# Motor_Driver_HIP4082_TPH1R403_Board_V2_0.net
KiCad netlist of a schematic drawn in Altium Designer
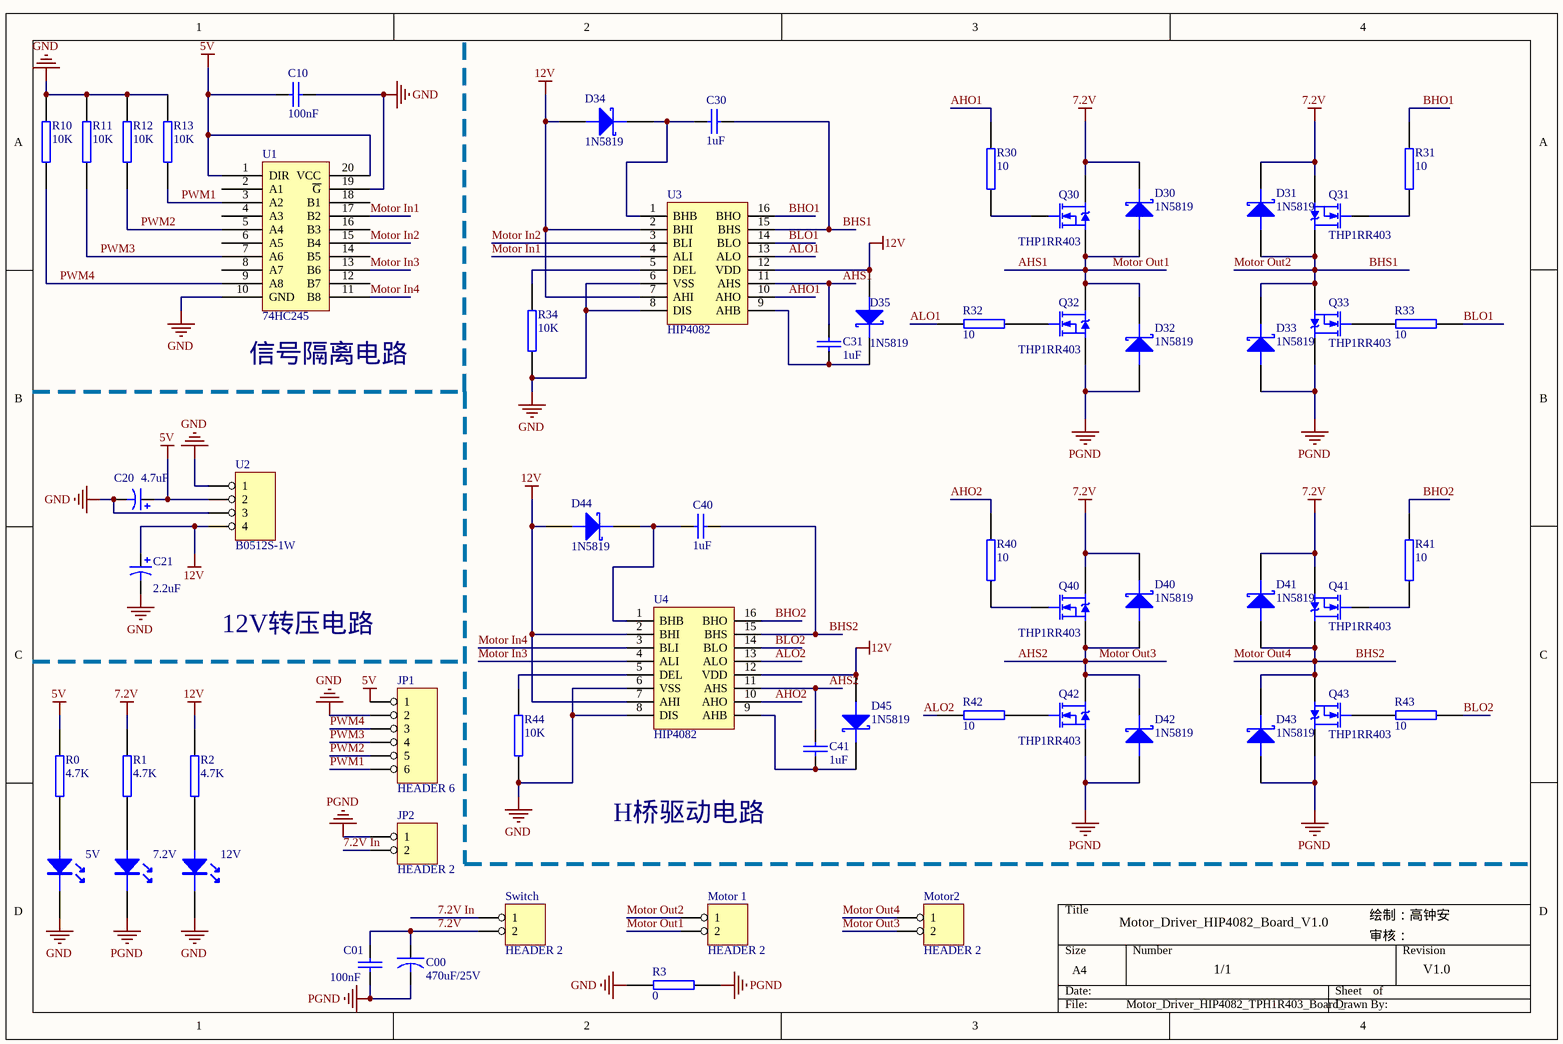
[diagram p0: Motor_Driver_HIP4082_TPH1R403_Board_V2.0.SchDoc]

(export (version "E")
  (design (tool "Eeschema 10.0.6"))
  (components
    (comp (ref "5V") (value "~") (footprint "0805_LED_S1") (libsource (lib "Protel99Lib_SCH") (part "LED")))
    (comp (ref "7.2V") (value "~") (footprint "0805_LED_S1") (libsource (lib "Protel99Lib_SCH") (part "LED")))
    (comp (ref "12V") (value "~") (footprint "0805_LED_S1") (libsource (lib "Protel99Lib_SCH") (part "LED")))
    (comp (ref "C00")
      (value "470uF/25V")
      (footprint "RB.2/.4")
      (description "Capacitor")
      (libsource (lib "Protel99Lib_SCH") (part "CAPACITOR"))
    )
    (comp (ref "C01")
      (value "100nF")
      (footprint "0805C")
      (description "Capacitor")
      (libsource (lib "Protel99Lib_SCH") (part "CAP"))
    )
    (comp (ref "C10")
      (value "100nF")
      (footprint "0603_C")
      (description "Capacitor")
      (libsource (lib "Protel99Lib_SCH") (part "CAP"))
    )
    (comp (ref "C20")
      (value "4.7uF")
      (footprint "3528")
      (description "Polarized Capacitor (Surface Mount)")
      (fields (field (name "PUBLISHER") "Altium Limited"))
      (libsource (lib "Miscellaneous Devices") (part "Cap Pol3"))
    )
    (comp (ref "C21")
      (value "2.2uF")
      (footprint "3528")
      (description "Polarized Capacitor (Surface Mount)")
      (fields (field (name "PUBLISHER") "Altium Limited"))
      (libsource (lib "Miscellaneous Devices") (part "Cap Pol3"))
    )
    (comp (ref "C30")
      (value "1uF")
      (footprint "0603C")
      (description "Capacitor")
      (libsource (lib "Protel99Lib_SCH") (part "CAP"))
    )
    (comp (ref "C31")
      (value "1uF")
      (footprint "0603C")
      (description "Capacitor")
      (libsource (lib "Protel99Lib_SCH") (part "CAP"))
    )
    (comp (ref "C40")
      (value "1uF")
      (footprint "0603_C")
      (description "Capacitor")
      (libsource (lib "Protel99Lib_SCH") (part "CAP"))
    )
    (comp (ref "C41")
      (value "1uF")
      (footprint "0603_C")
      (description "Capacitor")
      (libsource (lib "Protel99Lib_SCH") (part "CAP"))
    )
    (comp (ref "D30")
      (value "1N5819")
      (footprint "SOD-323")
      (description "Schottky Diode")
      (libsource (lib "Protel99Lib_SCH") (part "DIODE SCHOTTKY"))
    )
    (comp (ref "D31")
      (value "1N5819")
      (footprint "SOD-323")
      (description "Schottky Diode")
      (libsource (lib "Protel99Lib_SCH") (part "DIODE SCHOTTKY"))
    )
    (comp (ref "D32")
      (value "1N5819")
      (footprint "SOD-323")
      (description "Schottky Diode")
      (libsource (lib "Protel99Lib_SCH") (part "DIODE SCHOTTKY"))
    )
    (comp (ref "D33")
      (value "1N5819")
      (footprint "SOD-323")
      (description "Schottky Diode")
      (libsource (lib "Protel99Lib_SCH") (part "DIODE SCHOTTKY"))
    )
    (comp (ref "D34")
      (value "1N5819")
      (footprint "SOD-323")
      (description "Schottky Diode")
      (libsource (lib "Protel99Lib_SCH") (part "DIODE SCHOTTKY"))
    )
    (comp (ref "D35")
      (value "1N5819")
      (footprint "SOD-323")
      (description "Schottky Diode")
      (libsource (lib "Protel99Lib_SCH") (part "DIODE SCHOTTKY"))
    )
    (comp (ref "D40")
      (value "1N5819")
      (footprint "SOD-323")
      (description "Schottky Diode")
      (libsource (lib "Protel99Lib_SCH") (part "DIODE SCHOTTKY"))
    )
    (comp (ref "D41")
      (value "1N5819")
      (footprint "SOD-323")
      (description "Schottky Diode")
      (libsource (lib "Protel99Lib_SCH") (part "DIODE SCHOTTKY"))
    )
    (comp (ref "D42")
      (value "1N5819")
      (footprint "SOD-323")
      (description "Schottky Diode")
      (libsource (lib "Protel99Lib_SCH") (part "DIODE SCHOTTKY"))
    )
    (comp (ref "D43")
      (value "1N5819")
      (footprint "SOD-323")
      (description "Schottky Diode")
      (libsource (lib "Protel99Lib_SCH") (part "DIODE SCHOTTKY"))
    )
    (comp (ref "D44")
      (value "1N5819")
      (footprint "SOD-323")
      (description "Schottky Diode")
      (libsource (lib "Protel99Lib_SCH") (part "DIODE SCHOTTKY"))
    )
    (comp (ref "D45")
      (value "1N5819")
      (footprint "SOD-323")
      (description "Schottky Diode")
      (libsource (lib "Protel99Lib_SCH") (part "DIODE SCHOTTKY"))
    )
    (comp (ref "JP1")
      (value "HEADER 6")
      (footprint "SIP6N")
      (libsource (lib "Protel99Lib_SCH") (part "HEADER 6"))
    )
    (comp (ref "JP2")
      (value "HEADER 2")
      (footprint "T_Type_Adapter")
      (libsource (lib "Protel99Lib_SCH") (part "HEADER 2"))
    )
    (comp (ref "Motor 1")
      (value "HEADER 2")
      (footprint "KF301-2P")
      (libsource (lib "Protel99Lib_SCH") (part "HEADER 2"))
    )
    (comp (ref "Motor2")
      (value "HEADER 2")
      (footprint "KF301-2P")
      (libsource (lib "Protel99Lib_SCH") (part "HEADER 2"))
    )
    (comp (ref "Q30")
      (value "THP1RR403")
      (footprint "SOP_Advanced")
      (description "N-Channel MOSFET")
      (fields (field (name "PUBLISHER") "Altium Limited"))
      (libsource (lib "0.5 - 场效应管-可控硅") (part "MOSFET-N"))
    )
    (comp (ref "Q31")
      (value "THP1RR403")
      (footprint "SOP_Advanced")
      (description "N-Channel MOSFET")
      (fields (field (name "PUBLISHER") "Altium Limited"))
      (libsource (lib "0.5 - 场效应管-可控硅") (part "MOSFET-N"))
    )
    (comp (ref "Q32")
      (value "THP1RR403")
      (footprint "SOP_Advanced")
      (description "N-Channel MOSFET")
      (fields (field (name "PUBLISHER") "Altium Limited"))
      (libsource (lib "0.5 - 场效应管-可控硅") (part "MOSFET-N"))
    )
    (comp (ref "Q33")
      (value "THP1RR403")
      (footprint "SOP_Advanced")
      (description "N-Channel MOSFET")
      (fields (field (name "PUBLISHER") "Altium Limited"))
      (libsource (lib "0.5 - 场效应管-可控硅") (part "MOSFET-N"))
    )
    (comp (ref "Q40")
      (value "THP1RR403")
      (footprint "SOP_Advanced")
      (description "N-Channel MOSFET")
      (fields (field (name "PUBLISHER") "Altium Limited"))
      (libsource (lib "0.5 - 场效应管-可控硅") (part "MOSFET-N"))
    )
    (comp (ref "Q41")
      (value "THP1RR403")
      (footprint "SOP_Advanced")
      (description "N-Channel MOSFET")
      (fields (field (name "PUBLISHER") "Altium Limited"))
      (libsource (lib "0.5 - 场效应管-可控硅") (part "MOSFET-N"))
    )
    (comp (ref "Q42")
      (value "THP1RR403")
      (footprint "SOP_Advanced")
      (description "N-Channel MOSFET")
      (fields (field (name "PUBLISHER") "Altium Limited"))
      (libsource (lib "0.5 - 场效应管-可控硅") (part "MOSFET-N"))
    )
    (comp (ref "Q43")
      (value "THP1RR403")
      (footprint "SOP_Advanced")
      (description "N-Channel MOSFET")
      (fields (field (name "PUBLISHER") "Altium Limited"))
      (libsource (lib "0.5 - 场效应管-可控硅") (part "MOSFET-N"))
    )
    (comp (ref "R0") (value "4.7K") (footprint "0603_R") (libsource (lib "Protel99Lib_SCH") (part "RES2")))
    (comp (ref "R1") (value "4.7K") (footprint "0603_R") (libsource (lib "Protel99Lib_SCH") (part "RES2")))
    (comp (ref "R2") (value "4.7K") (footprint "0603_R") (libsource (lib "Protel99Lib_SCH") (part "RES2")))
    (comp (ref "R3") (value "0") (footprint "0805") (libsource (lib "Protel99Lib_SCH") (part "RES2")))
    (comp (ref "R10") (value "10K") (footprint "0603_R") (libsource (lib "") (part "RES2_1")))
    (comp (ref "R11") (value "10K") (footprint "0603_R") (libsource (lib "") (part "RES2_1")))
    (comp (ref "R12") (value "10K") (footprint "0603_R") (libsource (lib "") (part "RES2_1")))
    (comp (ref "R13") (value "10K") (footprint "0603_R") (libsource (lib "") (part "RES2_1")))
    (comp (ref "R30") (value "10") (footprint "0805") (libsource (lib "Protel99Lib_SCH") (part "RES2")))
    (comp (ref "R31") (value "10") (footprint "0805") (libsource (lib "Protel99Lib_SCH") (part "RES2")))
    (comp (ref "R32") (value "10") (footprint "0805") (libsource (lib "Protel99Lib_SCH") (part "RES2")))
    (comp (ref "R33") (value "10") (footprint "0805") (libsource (lib "Protel99Lib_SCH") (part "RES2")))
    (comp (ref "R34") (value "10K") (footprint "0603_R") (libsource (lib "Protel99Lib_SCH") (part "RES2")))
    (comp (ref "R40") (value "10") (footprint "0805") (libsource (lib "Protel99Lib_SCH") (part "RES2")))
    (comp (ref "R41") (value "10") (footprint "0805") (libsource (lib "Protel99Lib_SCH") (part "RES2")))
    (comp (ref "R42") (value "10") (footprint "0805") (libsource (lib "Protel99Lib_SCH") (part "RES2")))
    (comp (ref "R43") (value "10") (footprint "0805") (libsource (lib "Protel99Lib_SCH") (part "RES2")))
    (comp (ref "R44") (value "10K") (footprint "0603_R") (libsource (lib "Protel99Lib_SCH") (part "RES2")))
    (comp (ref "Switch")
      (value "HEADER 2")
      (footprint "SWITCH-MINI")
      (libsource (lib "Protel99Lib_SCH") (part "HEADER 2"))
    )
    (comp (ref "U1") (value "74HC245") (footprint "SOP20") (libsource (lib "BaseLib_SCH") (part "74HC245")))
    (comp (ref "U2")
      (value "B0512S-1W")
      (footprint "SIP4_B_S-1W")
      (description "4 Pin Header")
      (libsource (lib "Protel99Lib_SCH") (part "4 HEADER"))
    )
    (comp (ref "U3")
      (value "HIP4082")
      (footprint "SOP-16_208mil")
      (libsource (lib "Motor_Driver_HIP4082_Board_V1.0") (part "HIP4082"))
    )
    (comp (ref "U4")
      (value "HIP4082")
      (footprint "SOP-16_208mil")
      (libsource (lib "Motor_Driver_HIP4082_Board_V1.0") (part "HIP4082"))
    )
  )
  (nets
    (net (code "1") (name "/7.2V In") (class "Default")
      (node (ref "JP2") (pin "2") (pinfunction "2_2") (pintype "passive"))
      (node (ref "Switch") (pin "1") (pinfunction "1_1") (pintype "passive"))
    )
    (net (code "2") (name "/AHO1") (class "Default")
      (node (ref "R30") (pin "2") (pinfunction "2_2") (pintype "passive"))
      (node (ref "U3") (pin "10") (pinfunction "AHO_10") (pintype "passive"))
    )
    (net (code "3") (name "/AHO2") (class "Default")
      (node (ref "R40") (pin "2") (pinfunction "2_2") (pintype "passive"))
      (node (ref "U4") (pin "10") (pinfunction "AHO_10") (pintype "passive"))
    )
    (net (code "4") (name "/AHS1") (class "Default")
      (node (ref "C31") (pin "2") (pinfunction "2_2") (pintype "passive"))
      (node (ref "D30") (pin "1") (pinfunction "A_1") (pintype "passive"))
      (node (ref "D32") (pin "2") (pinfunction "K_2") (pintype "passive"))
      (node (ref "Motor 1") (pin "2") (pinfunction "2_2") (pintype "passive"))
      (node (ref "Q30") (pin "3") (pinfunction "S_3") (pintype "passive"))
      (node (ref "Q32") (pin "1") (pinfunction "D_1") (pintype "passive"))
      (node (ref "U3") (pin "11") (pinfunction "AHS_11") (pintype "passive"))
    )
    (net (code "5") (name "/AHS2") (class "Default")
      (node (ref "C41") (pin "2") (pinfunction "2_2") (pintype "passive"))
      (node (ref "D40") (pin "1") (pinfunction "A_1") (pintype "passive"))
      (node (ref "D42") (pin "2") (pinfunction "K_2") (pintype "passive"))
      (node (ref "Motor2") (pin "2") (pinfunction "2_2") (pintype "passive"))
      (node (ref "Q40") (pin "3") (pinfunction "S_3") (pintype "passive"))
      (node (ref "Q42") (pin "1") (pinfunction "D_1") (pintype "passive"))
      (node (ref "U4") (pin "11") (pinfunction "AHS_11") (pintype "passive"))
    )
    (net (code "6") (name "/ALO1") (class "Default")
      (node (ref "R32") (pin "2") (pinfunction "2_2") (pintype "passive"))
      (node (ref "U3") (pin "13") (pinfunction "ALO_13") (pintype "passive"))
    )
    (net (code "7") (name "/ALO2") (class "Default")
      (node (ref "R42") (pin "2") (pinfunction "2_2") (pintype "passive"))
      (node (ref "U4") (pin "13") (pinfunction "ALO_13") (pintype "passive"))
    )
    (net (code "8") (name "/BHO1") (class "Default")
      (node (ref "R31") (pin "2") (pinfunction "2_2") (pintype "passive"))
      (node (ref "U3") (pin "16") (pinfunction "BHO_16") (pintype "passive"))
    )
    (net (code "9") (name "/BHO2") (class "Default")
      (node (ref "R41") (pin "2") (pinfunction "2_2") (pintype "passive"))
      (node (ref "U4") (pin "16") (pinfunction "BHO_16") (pintype "passive"))
    )
    (net (code "10") (name "/BHS1") (class "Default")
      (node (ref "C30") (pin "2") (pinfunction "2_2") (pintype "passive"))
      (node (ref "D31") (pin "1") (pinfunction "A_1") (pintype "passive"))
      (node (ref "D33") (pin "2") (pinfunction "K_2") (pintype "passive"))
      (node (ref "Motor 1") (pin "1") (pinfunction "1_1") (pintype "passive"))
      (node (ref "Q31") (pin "1") (pinfunction "D_1") (pintype "passive"))
      (node (ref "Q33") (pin "3") (pinfunction "S_3") (pintype "passive"))
      (node (ref "U3") (pin "15") (pinfunction "BHS_15") (pintype "passive"))
    )
    (net (code "11") (name "/BHS2") (class "Default")
      (node (ref "C40") (pin "2") (pinfunction "2_2") (pintype "passive"))
      (node (ref "D41") (pin "1") (pinfunction "A_1") (pintype "passive"))
      (node (ref "D43") (pin "2") (pinfunction "K_2") (pintype "passive"))
      (node (ref "Motor2") (pin "1") (pinfunction "1_1") (pintype "passive"))
      (node (ref "Q41") (pin "1") (pinfunction "D_1") (pintype "passive"))
      (node (ref "Q43") (pin "3") (pinfunction "S_3") (pintype "passive"))
      (node (ref "U4") (pin "15") (pinfunction "BHS_15") (pintype "passive"))
    )
    (net (code "12") (name "/BLO1") (class "Default")
      (node (ref "R33") (pin "1") (pinfunction "1_1") (pintype "passive"))
      (node (ref "U3") (pin "14") (pinfunction "BLO_14") (pintype "passive"))
    )
    (net (code "13") (name "/BLO2") (class "Default")
      (node (ref "R43") (pin "1") (pinfunction "1_1") (pintype "passive"))
      (node (ref "U4") (pin "14") (pinfunction "BLO_14") (pintype "passive"))
    )
    (net (code "14") (name "/Motor In1") (class "Default")
      (node (ref "U1") (pin "17") (pinfunction "B2_17") (pintype "passive"))
      (node (ref "U3") (pin "4") (pinfunction "ALI_4") (pintype "passive"))
    )
    (net (code "15") (name "/Motor In2") (class "Default")
      (node (ref "U1") (pin "15") (pinfunction "B4_15") (pintype "passive"))
      (node (ref "U3") (pin "3") (pinfunction "BLI_3") (pintype "passive"))
    )
    (net (code "16") (name "/Motor In3") (class "Default")
      (node (ref "U1") (pin "13") (pinfunction "B6_13") (pintype "passive"))
      (node (ref "U4") (pin "4") (pinfunction "ALI_4") (pintype "passive"))
    )
    (net (code "17") (name "/Motor In4") (class "Default")
      (node (ref "U1") (pin "11") (pinfunction "B8_11") (pintype "passive"))
      (node (ref "U4") (pin "3") (pinfunction "BLI_3") (pintype "passive"))
    )
    (net (code "18") (name "/PWM1") (class "Default")
      (node (ref "JP1") (pin "6") (pinfunction "6_6") (pintype "passive"))
      (node (ref "R13") (pin "1") (pinfunction "1_1") (pintype "passive"))
      (node (ref "U1") (pin "3") (pinfunction "A2_3") (pintype "passive"))
    )
    (net (code "19") (name "/PWM2") (class "Default")
      (node (ref "JP1") (pin "5") (pinfunction "5_5") (pintype "passive"))
      (node (ref "R12") (pin "1") (pinfunction "1_1") (pintype "passive"))
      (node (ref "U1") (pin "5") (pinfunction "A4_5") (pintype "passive"))
    )
    (net (code "20") (name "/PWM3") (class "Default")
      (node (ref "JP1") (pin "4") (pinfunction "4_4") (pintype "passive"))
      (node (ref "R11") (pin "2") (pinfunction "2_2") (pintype "passive"))
      (node (ref "U1") (pin "7") (pinfunction "A6_7") (pintype "passive"))
    )
    (net (code "21") (name "/PWM4") (class "Default")
      (node (ref "JP1") (pin "3") (pinfunction "3_3") (pintype "passive"))
      (node (ref "R10") (pin "1") (pinfunction "1_1") (pintype "passive"))
      (node (ref "U1") (pin "9") (pinfunction "A8_9") (pintype "passive"))
    )
    (net (code "22") (name "5V") (class "Default")
      (node (ref "C10") (pin "1") (pinfunction "1_1") (pintype "passive"))
      (node (ref "C20") (pin "1") (pinfunction "1_1") (pintype "passive"))
      (node (ref "JP1") (pin "1") (pinfunction "1_1") (pintype "passive"))
      (node (ref "R0") (pin "2") (pinfunction "2_2") (pintype "passive"))
      (node (ref "U1") (pin "1") (pinfunction "DIR_1") (pintype "passive"))
      (node (ref "U1") (pin "20") (pinfunction "VCC_20") (pintype "passive"))
      (node (ref "U2") (pin "2") (pinfunction "2_2") (pintype "passive"))
    )
    (net (code "23") (name "7.2V") (class "Default")
      (node (ref "C00") (pin "1") (pinfunction "1_1") (pintype "passive"))
      (node (ref "C01") (pin "2") (pinfunction "2_2") (pintype "passive"))
      (node (ref "D30") (pin "2") (pinfunction "K_2") (pintype "passive"))
      (node (ref "D31") (pin "2") (pinfunction "K_2") (pintype "passive"))
      (node (ref "D40") (pin "2") (pinfunction "K_2") (pintype "passive"))
      (node (ref "D41") (pin "2") (pinfunction "K_2") (pintype "passive"))
      (node (ref "Q30") (pin "1") (pinfunction "D_1") (pintype "passive"))
      (node (ref "Q31") (pin "3") (pinfunction "S_3") (pintype "passive"))
      (node (ref "Q40") (pin "1") (pinfunction "D_1") (pintype "passive"))
      (node (ref "Q41") (pin "3") (pinfunction "S_3") (pintype "passive"))
      (node (ref "R1") (pin "2") (pinfunction "2_2") (pintype "passive"))
      (node (ref "Switch") (pin "2") (pinfunction "2_2") (pintype "passive"))
    )
    (net (code "24") (name "12V") (class "Default")
      (node (ref "C21") (pin "1") (pinfunction "1_1") (pintype "passive"))
      (node (ref "D34") (pin "1") (pinfunction "A_1") (pintype "passive"))
      (node (ref "D35") (pin "1") (pinfunction "A_1") (pintype "passive"))
      (node (ref "D44") (pin "1") (pinfunction "A_1") (pintype "passive"))
      (node (ref "D45") (pin "1") (pinfunction "A_1") (pintype "passive"))
      (node (ref "R2") (pin "2") (pinfunction "2_2") (pintype "passive"))
      (node (ref "U2") (pin "4") (pinfunction "4_4") (pintype "passive"))
      (node (ref "U3") (pin "12") (pinfunction "VDD_12") (pintype "passive"))
      (node (ref "U3") (pin "2") (pinfunction "BHI_2") (pintype "passive"))
      (node (ref "U3") (pin "7") (pinfunction "AHI_7") (pintype "passive"))
      (node (ref "U4") (pin "12") (pinfunction "VDD_12") (pintype "passive"))
      (node (ref "U4") (pin "2") (pinfunction "BHI_2") (pintype "passive"))
      (node (ref "U4") (pin "7") (pinfunction "AHI_7") (pintype "passive"))
    )
    (net (code "25") (name "GND") (class "Default")
      (node (ref "12V") (pin "K") (pinfunction "2_K") (pintype "passive"))
      (node (ref "5V") (pin "K") (pinfunction "2_K") (pintype "passive"))
      (node (ref "C10") (pin "2") (pinfunction "2_2") (pintype "passive"))
      (node (ref "C20") (pin "2") (pinfunction "2_2") (pintype "passive"))
      (node (ref "C21") (pin "2") (pinfunction "2_2") (pintype "passive"))
      (node (ref "JP1") (pin "2") (pinfunction "2_2") (pintype "passive"))
      (node (ref "R10") (pin "2") (pinfunction "2_2") (pintype "passive"))
      (node (ref "R11") (pin "1") (pinfunction "1_1") (pintype "passive"))
      (node (ref "R12") (pin "2") (pinfunction "2_2") (pintype "passive"))
      (node (ref "R13") (pin "2") (pinfunction "2_2") (pintype "passive"))
      (node (ref "R3") (pin "2") (pinfunction "2_2") (pintype "passive"))
      (node (ref "R34") (pin "1") (pinfunction "1_1") (pintype "passive"))
      (node (ref "R44") (pin "1") (pinfunction "1_1") (pintype "passive"))
      (node (ref "U1") (pin "10") (pinfunction "GND_10") (pintype "passive"))
      (node (ref "U1") (pin "19") (pinfunction "~{G}_19") (pintype "passive"))
      (node (ref "U2") (pin "1") (pinfunction "1_1") (pintype "passive"))
      (node (ref "U2") (pin "3") (pinfunction "3_3") (pintype "passive"))
      (node (ref "U3") (pin "6") (pinfunction "VSS_6") (pintype "passive"))
      (node (ref "U3") (pin "8") (pinfunction "DIS_8") (pintype "passive"))
      (node (ref "U4") (pin "6") (pinfunction "VSS_6") (pintype "passive"))
      (node (ref "U4") (pin "8") (pinfunction "DIS_8") (pintype "passive"))
    )
    (net (code "26") (name "Net-(5V-1)") (class "Default")
      (node (ref "5V") (pin "A") (pinfunction "1_A") (pintype "passive"))
      (node (ref "R0") (pin "1") (pinfunction "1_1") (pintype "passive"))
    )
    (net (code "27") (name "Net-(7.2V-1)") (class "Default")
      (node (ref "7.2V") (pin "A") (pinfunction "1_A") (pintype "passive"))
      (node (ref "R1") (pin "1") (pinfunction "1_1") (pintype "passive"))
    )
    (net (code "28") (name "Net-(12V-1)") (class "Default")
      (node (ref "12V") (pin "A") (pinfunction "1_A") (pintype "passive"))
      (node (ref "R2") (pin "1") (pinfunction "1_1") (pintype "passive"))
    )
    (net (code "29") (name "Net-(D34-K)") (class "Default")
      (node (ref "C30") (pin "1") (pinfunction "1_1") (pintype "passive"))
      (node (ref "D34") (pin "2") (pinfunction "K_2") (pintype "passive"))
      (node (ref "U3") (pin "1") (pinfunction "BHB_1") (pintype "passive"))
    )
    (net (code "30") (name "Net-(D35-K)") (class "Default")
      (node (ref "C31") (pin "1") (pinfunction "1_1") (pintype "passive"))
      (node (ref "D35") (pin "2") (pinfunction "K_2") (pintype "passive"))
      (node (ref "U3") (pin "9") (pinfunction "AHB_9") (pintype "passive"))
    )
    (net (code "31") (name "Net-(D44-K)") (class "Default")
      (node (ref "C40") (pin "1") (pinfunction "1_1") (pintype "passive"))
      (node (ref "D44") (pin "2") (pinfunction "K_2") (pintype "passive"))
      (node (ref "U4") (pin "1") (pinfunction "BHB_1") (pintype "passive"))
    )
    (net (code "32") (name "Net-(D45-K)") (class "Default")
      (node (ref "C41") (pin "1") (pinfunction "1_1") (pintype "passive"))
      (node (ref "D45") (pin "2") (pinfunction "K_2") (pintype "passive"))
      (node (ref "U4") (pin "9") (pinfunction "AHB_9") (pintype "passive"))
    )
    (net (code "33") (name "Net-(Q30-G)") (class "Default")
      (node (ref "Q30") (pin "2") (pinfunction "G_2") (pintype "passive"))
      (node (ref "R30") (pin "1") (pinfunction "1_1") (pintype "passive"))
    )
    (net (code "34") (name "Net-(Q31-G)") (class "Default")
      (node (ref "Q31") (pin "2") (pinfunction "G_2") (pintype "passive"))
      (node (ref "R31") (pin "1") (pinfunction "1_1") (pintype "passive"))
    )
    (net (code "35") (name "Net-(Q32-G)") (class "Default")
      (node (ref "Q32") (pin "2") (pinfunction "G_2") (pintype "passive"))
      (node (ref "R32") (pin "1") (pinfunction "1_1") (pintype "passive"))
    )
    (net (code "36") (name "Net-(Q33-G)") (class "Default")
      (node (ref "Q33") (pin "2") (pinfunction "G_2") (pintype "passive"))
      (node (ref "R33") (pin "2") (pinfunction "2_2") (pintype "passive"))
    )
    (net (code "37") (name "Net-(Q40-G)") (class "Default")
      (node (ref "Q40") (pin "2") (pinfunction "G_2") (pintype "passive"))
      (node (ref "R40") (pin "1") (pinfunction "1_1") (pintype "passive"))
    )
    (net (code "38") (name "Net-(Q41-G)") (class "Default")
      (node (ref "Q41") (pin "2") (pinfunction "G_2") (pintype "passive"))
      (node (ref "R41") (pin "1") (pinfunction "1_1") (pintype "passive"))
    )
    (net (code "39") (name "Net-(Q42-G)") (class "Default")
      (node (ref "Q42") (pin "2") (pinfunction "G_2") (pintype "passive"))
      (node (ref "R42") (pin "1") (pinfunction "1_1") (pintype "passive"))
    )
    (net (code "40") (name "Net-(Q43-G)") (class "Default")
      (node (ref "Q43") (pin "2") (pinfunction "G_2") (pintype "passive"))
      (node (ref "R43") (pin "2") (pinfunction "2_2") (pintype "passive"))
    )
    (net (code "41") (name "Net-(U3-DEL)") (class "Default")
      (node (ref "R34") (pin "2") (pinfunction "2_2") (pintype "passive"))
      (node (ref "U3") (pin "5") (pinfunction "DEL_5") (pintype "passive"))
    )
    (net (code "42") (name "Net-(U4-DEL)") (class "Default")
      (node (ref "R44") (pin "2") (pinfunction "2_2") (pintype "passive"))
      (node (ref "U4") (pin "5") (pinfunction "DEL_5") (pintype "passive"))
    )
    (net (code "43") (name "PGND") (class "Default")
      (node (ref "7.2V") (pin "K") (pinfunction "2_K") (pintype "passive"))
      (node (ref "C00") (pin "2") (pinfunction "2_2") (pintype "passive"))
      (node (ref "C01") (pin "1") (pinfunction "1_1") (pintype "passive"))
      (node (ref "D32") (pin "1") (pinfunction "A_1") (pintype "passive"))
      (node (ref "D33") (pin "1") (pinfunction "A_1") (pintype "passive"))
      (node (ref "D42") (pin "1") (pinfunction "A_1") (pintype "passive"))
      (node (ref "D43") (pin "1") (pinfunction "A_1") (pintype "passive"))
      (node (ref "JP2") (pin "1") (pinfunction "1_1") (pintype "passive"))
      (node (ref "Q32") (pin "3") (pinfunction "S_3") (pintype "passive"))
      (node (ref "Q33") (pin "1") (pinfunction "D_1") (pintype "passive"))
      (node (ref "Q42") (pin "3") (pinfunction "S_3") (pintype "passive"))
      (node (ref "Q43") (pin "1") (pinfunction "D_1") (pintype "passive"))
      (node (ref "R3") (pin "1") (pinfunction "1_1") (pintype "passive"))
    )
    (net (code "44") (name "unconnected-(U1-A1-Pad2)") (class "Default")
      (node (ref "U1") (pin "2") (pinfunction "A1_2") (pintype "passive"))
    )
    (net (code "45") (name "unconnected-(U1-A3-Pad4)") (class "Default")
      (node (ref "U1") (pin "4") (pinfunction "A3_4") (pintype "passive"))
    )
    (net (code "46") (name "unconnected-(U1-A5-Pad6)") (class "Default")
      (node (ref "U1") (pin "6") (pinfunction "A5_6") (pintype "passive"))
    )
    (net (code "47") (name "unconnected-(U1-A7-Pad8)") (class "Default")
      (node (ref "U1") (pin "8") (pinfunction "A7_8") (pintype "passive"))
    )
    (net (code "48") (name "unconnected-(U1-B1-Pad18)") (class "Default")
      (node (ref "U1") (pin "18") (pinfunction "B1_18") (pintype "passive"))
    )
    (net (code "49") (name "unconnected-(U1-B3-Pad16)") (class "Default")
      (node (ref "U1") (pin "16") (pinfunction "B3_16") (pintype "passive"))
    )
    (net (code "50") (name "unconnected-(U1-B5-Pad14)") (class "Default")
      (node (ref "U1") (pin "14") (pinfunction "B5_14") (pintype "passive"))
    )
    (net (code "51") (name "unconnected-(U1-B7-Pad12)") (class "Default")
      (node (ref "U1") (pin "12") (pinfunction "B7_12") (pintype "passive"))
    )
  )
)
